# 09-NORStatusLed.net
KiCad netlist of a schematic drawn in Altium Designer
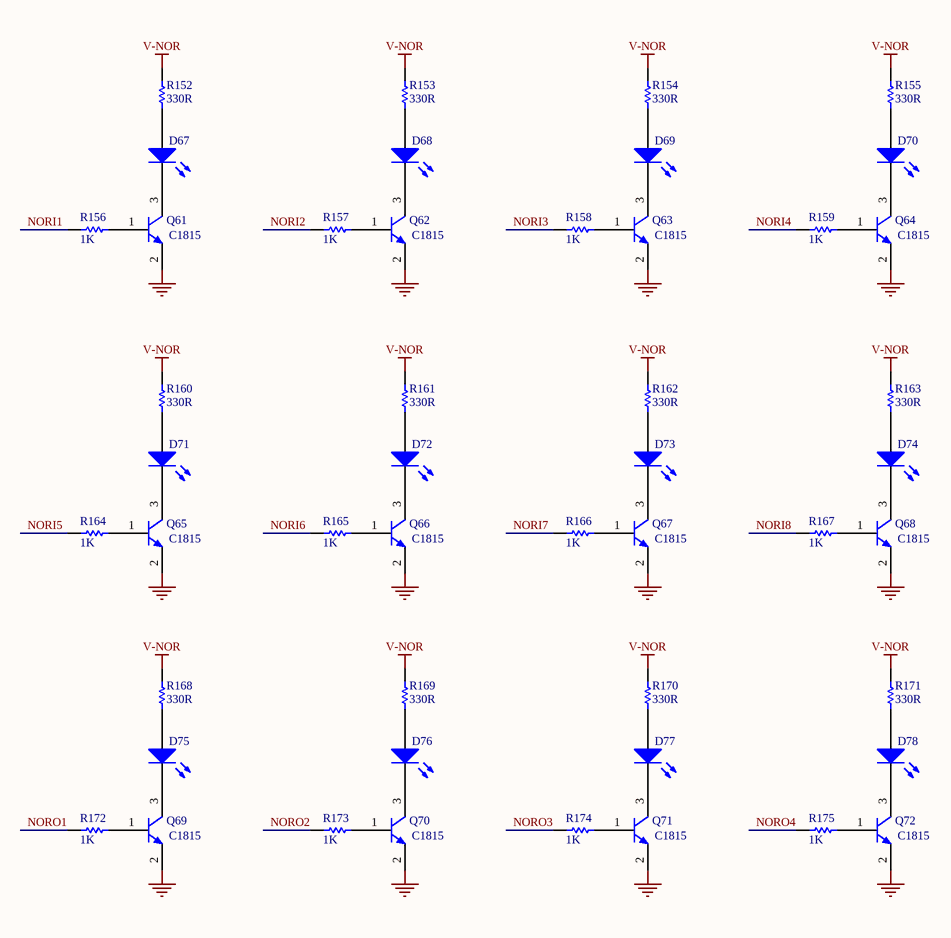
[diagram p0: 09-NORStatusLed.SchDoc]

(export (version "E")
  (design (tool "Eeschema 10.0.6"))
  (components
    (comp (ref "D67")
      (value "LED")
      (footprint "LED-3528")
      (description "Typical RED, GREEN, YELLOW, AMBER GaAs LED")
      (fields (field (name "PUBLISHER") "Altium Limited"))
      (libsource (lib "Miscellaneous Devices") (part "LED2"))
    )
    (comp (ref "D68")
      (value "LED")
      (footprint "LED-3528")
      (description "Typical RED, GREEN, YELLOW, AMBER GaAs LED")
      (fields (field (name "PUBLISHER") "Altium Limited"))
      (libsource (lib "Miscellaneous Devices") (part "LED2"))
    )
    (comp (ref "D69")
      (value "LED")
      (footprint "LED-3528")
      (description "Typical RED, GREEN, YELLOW, AMBER GaAs LED")
      (fields (field (name "PUBLISHER") "Altium Limited"))
      (libsource (lib "Miscellaneous Devices") (part "LED2"))
    )
    (comp (ref "D70")
      (value "LED")
      (footprint "LED-3528")
      (description "Typical RED, GREEN, YELLOW, AMBER GaAs LED")
      (fields (field (name "PUBLISHER") "Altium Limited"))
      (libsource (lib "Miscellaneous Devices") (part "LED2"))
    )
    (comp (ref "D71")
      (value "LED")
      (footprint "LED-3528")
      (description "Typical RED, GREEN, YELLOW, AMBER GaAs LED")
      (fields (field (name "PUBLISHER") "Altium Limited"))
      (libsource (lib "Miscellaneous Devices") (part "LED2"))
    )
    (comp (ref "D72")
      (value "LED")
      (footprint "LED-3528")
      (description "Typical RED, GREEN, YELLOW, AMBER GaAs LED")
      (fields (field (name "PUBLISHER") "Altium Limited"))
      (libsource (lib "Miscellaneous Devices") (part "LED2"))
    )
    (comp (ref "D73")
      (value "LED")
      (footprint "LED-3528")
      (description "Typical RED, GREEN, YELLOW, AMBER GaAs LED")
      (fields (field (name "PUBLISHER") "Altium Limited"))
      (libsource (lib "Miscellaneous Devices") (part "LED2"))
    )
    (comp (ref "D74")
      (value "LED")
      (footprint "LED-3528")
      (description "Typical RED, GREEN, YELLOW, AMBER GaAs LED")
      (fields (field (name "PUBLISHER") "Altium Limited"))
      (libsource (lib "Miscellaneous Devices") (part "LED2"))
    )
    (comp (ref "D75")
      (value "LED")
      (footprint "LED-3528")
      (description "Typical RED, GREEN, YELLOW, AMBER GaAs LED")
      (fields (field (name "PUBLISHER") "Altium Limited"))
      (libsource (lib "Miscellaneous Devices") (part "LED2"))
    )
    (comp (ref "D76")
      (value "LED")
      (footprint "LED-3528")
      (description "Typical RED, GREEN, YELLOW, AMBER GaAs LED")
      (fields (field (name "PUBLISHER") "Altium Limited"))
      (libsource (lib "Miscellaneous Devices") (part "LED2"))
    )
    (comp (ref "D77")
      (value "LED")
      (footprint "LED-3528")
      (description "Typical RED, GREEN, YELLOW, AMBER GaAs LED")
      (fields (field (name "PUBLISHER") "Altium Limited"))
      (libsource (lib "Miscellaneous Devices") (part "LED2"))
    )
    (comp (ref "D78")
      (value "LED")
      (footprint "LED-3528")
      (description "Typical RED, GREEN, YELLOW, AMBER GaAs LED")
      (fields (field (name "PUBLISHER") "Altium Limited"))
      (libsource (lib "Miscellaneous Devices") (part "LED2"))
    )
    (comp (ref "Q61")
      (value "C1815")
      (footprint "SOT23-321")
      (description "NPN Bipolar Transistor")
      (fields (field (name "Comment") "C1815-SMD"))
      (libsource (lib "Miscellaneous Devices") (part "NPN"))
    )
    (comp (ref "Q62")
      (value "C1815")
      (footprint "SOT23-321")
      (description "NPN Bipolar Transistor")
      (fields (field (name "Comment") "C1815-SMD"))
      (libsource (lib "Miscellaneous Devices") (part "NPN"))
    )
    (comp (ref "Q63")
      (value "C1815")
      (footprint "SOT23-321")
      (description "NPN Bipolar Transistor")
      (fields (field (name "Comment") "C1815-SMD"))
      (libsource (lib "Miscellaneous Devices") (part "NPN"))
    )
    (comp (ref "Q64")
      (value "C1815")
      (footprint "SOT23-321")
      (description "NPN Bipolar Transistor")
      (fields (field (name "Comment") "C1815-SMD"))
      (libsource (lib "Miscellaneous Devices") (part "NPN"))
    )
    (comp (ref "Q65")
      (value "C1815")
      (footprint "SOT23-321")
      (description "NPN Bipolar Transistor")
      (fields (field (name "Comment") "C1815-SMD"))
      (libsource (lib "Miscellaneous Devices") (part "NPN"))
    )
    (comp (ref "Q66")
      (value "C1815")
      (footprint "SOT23-321")
      (description "NPN Bipolar Transistor")
      (fields (field (name "Comment") "C1815-SMD"))
      (libsource (lib "Miscellaneous Devices") (part "NPN"))
    )
    (comp (ref "Q67")
      (value "C1815")
      (footprint "SOT23-321")
      (description "NPN Bipolar Transistor")
      (fields (field (name "Comment") "C1815-SMD"))
      (libsource (lib "Miscellaneous Devices") (part "NPN"))
    )
    (comp (ref "Q68")
      (value "C1815")
      (footprint "SOT23-321")
      (description "NPN Bipolar Transistor")
      (fields (field (name "Comment") "C1815-SMD"))
      (libsource (lib "Miscellaneous Devices") (part "NPN"))
    )
    (comp (ref "Q69")
      (value "C1815")
      (footprint "SOT23-321")
      (description "NPN Bipolar Transistor")
      (fields (field (name "Comment") "C1815-SMD"))
      (libsource (lib "Miscellaneous Devices") (part "NPN"))
    )
    (comp (ref "Q70")
      (value "C1815")
      (footprint "SOT23-321")
      (description "NPN Bipolar Transistor")
      (fields (field (name "Comment") "C1815-SMD"))
      (libsource (lib "Miscellaneous Devices") (part "NPN"))
    )
    (comp (ref "Q71")
      (value "C1815")
      (footprint "SOT23-321")
      (description "NPN Bipolar Transistor")
      (fields (field (name "Comment") "C1815-SMD"))
      (libsource (lib "Miscellaneous Devices") (part "NPN"))
    )
    (comp (ref "Q72")
      (value "C1815")
      (footprint "SOT23-321")
      (description "NPN Bipolar Transistor")
      (fields (field (name "Comment") "C1815-SMD"))
      (libsource (lib "Miscellaneous Devices") (part "NPN"))
    )
    (comp (ref "R152")
      (value "330R")
      (footprint "R-0805")
      (description "Resistor")
      (fields (field (name "PUBLISHER") "Altium Limited"))
      (libsource (lib "Miscellaneous Devices") (part "Res1"))
    )
    (comp (ref "R153")
      (value "330R")
      (footprint "R-0805")
      (description "Resistor")
      (fields (field (name "PUBLISHER") "Altium Limited"))
      (libsource (lib "Miscellaneous Devices") (part "Res1"))
    )
    (comp (ref "R154")
      (value "330R")
      (footprint "R-0805")
      (description "Resistor")
      (fields (field (name "PUBLISHER") "Altium Limited"))
      (libsource (lib "Miscellaneous Devices") (part "Res1"))
    )
    (comp (ref "R155")
      (value "330R")
      (footprint "R-0805")
      (description "Resistor")
      (fields (field (name "PUBLISHER") "Altium Limited"))
      (libsource (lib "Miscellaneous Devices") (part "Res1"))
    )
    (comp (ref "R156")
      (value "1K")
      (footprint "R-0805")
      (description "Resistor")
      (fields (field (name "PUBLISHER") "Altium Limited"))
      (libsource (lib "Miscellaneous Devices") (part "Res1"))
    )
    (comp (ref "R157")
      (value "1K")
      (footprint "R-0805")
      (description "Resistor")
      (fields (field (name "PUBLISHER") "Altium Limited"))
      (libsource (lib "Miscellaneous Devices") (part "Res1"))
    )
    (comp (ref "R158")
      (value "1K")
      (footprint "R-0805")
      (description "Resistor")
      (fields (field (name "PUBLISHER") "Altium Limited"))
      (libsource (lib "Miscellaneous Devices") (part "Res1"))
    )
    (comp (ref "R159")
      (value "1K")
      (footprint "R-0805")
      (description "Resistor")
      (fields (field (name "PUBLISHER") "Altium Limited"))
      (libsource (lib "Miscellaneous Devices") (part "Res1"))
    )
    (comp (ref "R160")
      (value "330R")
      (footprint "R-0805")
      (description "Resistor")
      (fields (field (name "PUBLISHER") "Altium Limited"))
      (libsource (lib "Miscellaneous Devices") (part "Res1"))
    )
    (comp (ref "R161")
      (value "330R")
      (footprint "R-0805")
      (description "Resistor")
      (fields (field (name "PUBLISHER") "Altium Limited"))
      (libsource (lib "Miscellaneous Devices") (part "Res1"))
    )
    (comp (ref "R162")
      (value "330R")
      (footprint "R-0805")
      (description "Resistor")
      (fields (field (name "PUBLISHER") "Altium Limited"))
      (libsource (lib "Miscellaneous Devices") (part "Res1"))
    )
    (comp (ref "R163")
      (value "330R")
      (footprint "R-0805")
      (description "Resistor")
      (fields (field (name "PUBLISHER") "Altium Limited"))
      (libsource (lib "Miscellaneous Devices") (part "Res1"))
    )
    (comp (ref "R164")
      (value "1K")
      (footprint "R-0805")
      (description "Resistor")
      (fields (field (name "PUBLISHER") "Altium Limited"))
      (libsource (lib "Miscellaneous Devices") (part "Res1"))
    )
    (comp (ref "R165")
      (value "1K")
      (footprint "R-0805")
      (description "Resistor")
      (fields (field (name "PUBLISHER") "Altium Limited"))
      (libsource (lib "Miscellaneous Devices") (part "Res1"))
    )
    (comp (ref "R166")
      (value "1K")
      (footprint "R-0805")
      (description "Resistor")
      (fields (field (name "PUBLISHER") "Altium Limited"))
      (libsource (lib "Miscellaneous Devices") (part "Res1"))
    )
    (comp (ref "R167")
      (value "1K")
      (footprint "R-0805")
      (description "Resistor")
      (fields (field (name "PUBLISHER") "Altium Limited"))
      (libsource (lib "Miscellaneous Devices") (part "Res1"))
    )
    (comp (ref "R168")
      (value "330R")
      (footprint "R-0805")
      (description "Resistor")
      (fields (field (name "PUBLISHER") "Altium Limited"))
      (libsource (lib "Miscellaneous Devices") (part "Res1"))
    )
    (comp (ref "R169")
      (value "330R")
      (footprint "R-0805")
      (description "Resistor")
      (fields (field (name "PUBLISHER") "Altium Limited"))
      (libsource (lib "Miscellaneous Devices") (part "Res1"))
    )
    (comp (ref "R170")
      (value "330R")
      (footprint "R-0805")
      (description "Resistor")
      (fields (field (name "PUBLISHER") "Altium Limited"))
      (libsource (lib "Miscellaneous Devices") (part "Res1"))
    )
    (comp (ref "R171")
      (value "330R")
      (footprint "R-0805")
      (description "Resistor")
      (fields (field (name "PUBLISHER") "Altium Limited"))
      (libsource (lib "Miscellaneous Devices") (part "Res1"))
    )
    (comp (ref "R172")
      (value "1K")
      (footprint "R-0805")
      (description "Resistor")
      (fields (field (name "PUBLISHER") "Altium Limited"))
      (libsource (lib "Miscellaneous Devices") (part "Res1"))
    )
    (comp (ref "R173")
      (value "1K")
      (footprint "R-0805")
      (description "Resistor")
      (fields (field (name "PUBLISHER") "Altium Limited"))
      (libsource (lib "Miscellaneous Devices") (part "Res1"))
    )
    (comp (ref "R174")
      (value "1K")
      (footprint "R-0805")
      (description "Resistor")
      (fields (field (name "PUBLISHER") "Altium Limited"))
      (libsource (lib "Miscellaneous Devices") (part "Res1"))
    )
    (comp (ref "R175")
      (value "1K")
      (footprint "R-0805")
      (description "Resistor")
      (fields (field (name "PUBLISHER") "Altium Limited"))
      (libsource (lib "Miscellaneous Devices") (part "Res1"))
    )
  )
  (nets
    (net (code "1") (name "/NORI1") (class "Default")
      (node (ref "R156") (pin "2") (pinfunction "2_2") (pintype "passive"))
    )
    (net (code "2") (name "/NORI2") (class "Default")
      (node (ref "R157") (pin "2") (pinfunction "2_2") (pintype "passive"))
    )
    (net (code "3") (name "/NORI3") (class "Default")
      (node (ref "R158") (pin "2") (pinfunction "2_2") (pintype "passive"))
    )
    (net (code "4") (name "/NORI4") (class "Default")
      (node (ref "R159") (pin "2") (pinfunction "2_2") (pintype "passive"))
    )
    (net (code "5") (name "/NORI5") (class "Default")
      (node (ref "R164") (pin "2") (pinfunction "2_2") (pintype "passive"))
    )
    (net (code "6") (name "/NORI6") (class "Default")
      (node (ref "R165") (pin "2") (pinfunction "2_2") (pintype "passive"))
    )
    (net (code "7") (name "/NORI7") (class "Default")
      (node (ref "R166") (pin "2") (pinfunction "2_2") (pintype "passive"))
    )
    (net (code "8") (name "/NORI8") (class "Default")
      (node (ref "R167") (pin "2") (pinfunction "2_2") (pintype "passive"))
    )
    (net (code "9") (name "/NORO1") (class "Default")
      (node (ref "R172") (pin "2") (pinfunction "2_2") (pintype "passive"))
    )
    (net (code "10") (name "/NORO2") (class "Default")
      (node (ref "R173") (pin "2") (pinfunction "2_2") (pintype "passive"))
    )
    (net (code "11") (name "/NORO3") (class "Default")
      (node (ref "R174") (pin "2") (pinfunction "2_2") (pintype "passive"))
    )
    (net (code "12") (name "/NORO4") (class "Default")
      (node (ref "R175") (pin "2") (pinfunction "2_2") (pintype "passive"))
    )
    (net (code "13") (name "GND") (class "Default")
      (node (ref "Q61") (pin "2") (pinfunction "E_2") (pintype "passive"))
      (node (ref "Q62") (pin "2") (pinfunction "E_2") (pintype "passive"))
      (node (ref "Q63") (pin "2") (pinfunction "E_2") (pintype "passive"))
      (node (ref "Q64") (pin "2") (pinfunction "E_2") (pintype "passive"))
      (node (ref "Q65") (pin "2") (pinfunction "E_2") (pintype "passive"))
      (node (ref "Q66") (pin "2") (pinfunction "E_2") (pintype "passive"))
      (node (ref "Q67") (pin "2") (pinfunction "E_2") (pintype "passive"))
      (node (ref "Q68") (pin "2") (pinfunction "E_2") (pintype "passive"))
      (node (ref "Q69") (pin "2") (pinfunction "E_2") (pintype "passive"))
      (node (ref "Q70") (pin "2") (pinfunction "E_2") (pintype "passive"))
      (node (ref "Q71") (pin "2") (pinfunction "E_2") (pintype "passive"))
      (node (ref "Q72") (pin "2") (pinfunction "E_2") (pintype "passive"))
    )
    (net (code "14") (name "Net-(D67-A)") (class "Default")
      (node (ref "D67") (pin "1") (pinfunction "A_1") (pintype "passive"))
      (node (ref "R152") (pin "1") (pinfunction "1_1") (pintype "passive"))
    )
    (net (code "15") (name "Net-(D67-K)") (class "Default")
      (node (ref "D67") (pin "2") (pinfunction "K_2") (pintype "passive"))
      (node (ref "Q61") (pin "3") (pinfunction "C_3") (pintype "passive"))
    )
    (net (code "16") (name "Net-(D68-A)") (class "Default")
      (node (ref "D68") (pin "1") (pinfunction "A_1") (pintype "passive"))
      (node (ref "R153") (pin "1") (pinfunction "1_1") (pintype "passive"))
    )
    (net (code "17") (name "Net-(D68-K)") (class "Default")
      (node (ref "D68") (pin "2") (pinfunction "K_2") (pintype "passive"))
      (node (ref "Q62") (pin "3") (pinfunction "C_3") (pintype "passive"))
    )
    (net (code "18") (name "Net-(D69-A)") (class "Default")
      (node (ref "D69") (pin "1") (pinfunction "A_1") (pintype "passive"))
      (node (ref "R154") (pin "1") (pinfunction "1_1") (pintype "passive"))
    )
    (net (code "19") (name "Net-(D69-K)") (class "Default")
      (node (ref "D69") (pin "2") (pinfunction "K_2") (pintype "passive"))
      (node (ref "Q63") (pin "3") (pinfunction "C_3") (pintype "passive"))
    )
    (net (code "20") (name "Net-(D70-A)") (class "Default")
      (node (ref "D70") (pin "1") (pinfunction "A_1") (pintype "passive"))
      (node (ref "R155") (pin "1") (pinfunction "1_1") (pintype "passive"))
    )
    (net (code "21") (name "Net-(D70-K)") (class "Default")
      (node (ref "D70") (pin "2") (pinfunction "K_2") (pintype "passive"))
      (node (ref "Q64") (pin "3") (pinfunction "C_3") (pintype "passive"))
    )
    (net (code "22") (name "Net-(D71-A)") (class "Default")
      (node (ref "D71") (pin "1") (pinfunction "A_1") (pintype "passive"))
      (node (ref "R160") (pin "1") (pinfunction "1_1") (pintype "passive"))
    )
    (net (code "23") (name "Net-(D71-K)") (class "Default")
      (node (ref "D71") (pin "2") (pinfunction "K_2") (pintype "passive"))
      (node (ref "Q65") (pin "3") (pinfunction "C_3") (pintype "passive"))
    )
    (net (code "24") (name "Net-(D72-A)") (class "Default")
      (node (ref "D72") (pin "1") (pinfunction "A_1") (pintype "passive"))
      (node (ref "R161") (pin "1") (pinfunction "1_1") (pintype "passive"))
    )
    (net (code "25") (name "Net-(D72-K)") (class "Default")
      (node (ref "D72") (pin "2") (pinfunction "K_2") (pintype "passive"))
      (node (ref "Q66") (pin "3") (pinfunction "C_3") (pintype "passive"))
    )
    (net (code "26") (name "Net-(D73-A)") (class "Default")
      (node (ref "D73") (pin "1") (pinfunction "A_1") (pintype "passive"))
      (node (ref "R162") (pin "1") (pinfunction "1_1") (pintype "passive"))
    )
    (net (code "27") (name "Net-(D73-K)") (class "Default")
      (node (ref "D73") (pin "2") (pinfunction "K_2") (pintype "passive"))
      (node (ref "Q67") (pin "3") (pinfunction "C_3") (pintype "passive"))
    )
    (net (code "28") (name "Net-(D74-A)") (class "Default")
      (node (ref "D74") (pin "1") (pinfunction "A_1") (pintype "passive"))
      (node (ref "R163") (pin "1") (pinfunction "1_1") (pintype "passive"))
    )
    (net (code "29") (name "Net-(D74-K)") (class "Default")
      (node (ref "D74") (pin "2") (pinfunction "K_2") (pintype "passive"))
      (node (ref "Q68") (pin "3") (pinfunction "C_3") (pintype "passive"))
    )
    (net (code "30") (name "Net-(D75-A)") (class "Default")
      (node (ref "D75") (pin "1") (pinfunction "A_1") (pintype "passive"))
      (node (ref "R168") (pin "1") (pinfunction "1_1") (pintype "passive"))
    )
    (net (code "31") (name "Net-(D75-K)") (class "Default")
      (node (ref "D75") (pin "2") (pinfunction "K_2") (pintype "passive"))
      (node (ref "Q69") (pin "3") (pinfunction "C_3") (pintype "passive"))
    )
    (net (code "32") (name "Net-(D76-A)") (class "Default")
      (node (ref "D76") (pin "1") (pinfunction "A_1") (pintype "passive"))
      (node (ref "R169") (pin "1") (pinfunction "1_1") (pintype "passive"))
    )
    (net (code "33") (name "Net-(D76-K)") (class "Default")
      (node (ref "D76") (pin "2") (pinfunction "K_2") (pintype "passive"))
      (node (ref "Q70") (pin "3") (pinfunction "C_3") (pintype "passive"))
    )
    (net (code "34") (name "Net-(D77-A)") (class "Default")
      (node (ref "D77") (pin "1") (pinfunction "A_1") (pintype "passive"))
      (node (ref "R170") (pin "1") (pinfunction "1_1") (pintype "passive"))
    )
    (net (code "35") (name "Net-(D77-K)") (class "Default")
      (node (ref "D77") (pin "2") (pinfunction "K_2") (pintype "passive"))
      (node (ref "Q71") (pin "3") (pinfunction "C_3") (pintype "passive"))
    )
    (net (code "36") (name "Net-(D78-A)") (class "Default")
      (node (ref "D78") (pin "1") (pinfunction "A_1") (pintype "passive"))
      (node (ref "R171") (pin "1") (pinfunction "1_1") (pintype "passive"))
    )
    (net (code "37") (name "Net-(D78-K)") (class "Default")
      (node (ref "D78") (pin "2") (pinfunction "K_2") (pintype "passive"))
      (node (ref "Q72") (pin "3") (pinfunction "C_3") (pintype "passive"))
    )
    (net (code "38") (name "Net-(Q61-B)") (class "Default")
      (node (ref "Q61") (pin "1") (pinfunction "B_1") (pintype "passive"))
      (node (ref "R156") (pin "1") (pinfunction "1_1") (pintype "passive"))
    )
    (net (code "39") (name "Net-(Q62-B)") (class "Default")
      (node (ref "Q62") (pin "1") (pinfunction "B_1") (pintype "passive"))
      (node (ref "R157") (pin "1") (pinfunction "1_1") (pintype "passive"))
    )
    (net (code "40") (name "Net-(Q63-B)") (class "Default")
      (node (ref "Q63") (pin "1") (pinfunction "B_1") (pintype "passive"))
      (node (ref "R158") (pin "1") (pinfunction "1_1") (pintype "passive"))
    )
    (net (code "41") (name "Net-(Q64-B)") (class "Default")
      (node (ref "Q64") (pin "1") (pinfunction "B_1") (pintype "passive"))
      (node (ref "R159") (pin "1") (pinfunction "1_1") (pintype "passive"))
    )
    (net (code "42") (name "Net-(Q65-B)") (class "Default")
      (node (ref "Q65") (pin "1") (pinfunction "B_1") (pintype "passive"))
      (node (ref "R164") (pin "1") (pinfunction "1_1") (pintype "passive"))
    )
    (net (code "43") (name "Net-(Q66-B)") (class "Default")
      (node (ref "Q66") (pin "1") (pinfunction "B_1") (pintype "passive"))
      (node (ref "R165") (pin "1") (pinfunction "1_1") (pintype "passive"))
    )
    (net (code "44") (name "Net-(Q67-B)") (class "Default")
      (node (ref "Q67") (pin "1") (pinfunction "B_1") (pintype "passive"))
      (node (ref "R166") (pin "1") (pinfunction "1_1") (pintype "passive"))
    )
    (net (code "45") (name "Net-(Q68-B)") (class "Default")
      (node (ref "Q68") (pin "1") (pinfunction "B_1") (pintype "passive"))
      (node (ref "R167") (pin "1") (pinfunction "1_1") (pintype "passive"))
    )
    (net (code "46") (name "Net-(Q69-B)") (class "Default")
      (node (ref "Q69") (pin "1") (pinfunction "B_1") (pintype "passive"))
      (node (ref "R172") (pin "1") (pinfunction "1_1") (pintype "passive"))
    )
    (net (code "47") (name "Net-(Q70-B)") (class "Default")
      (node (ref "Q70") (pin "1") (pinfunction "B_1") (pintype "passive"))
      (node (ref "R173") (pin "1") (pinfunction "1_1") (pintype "passive"))
    )
    (net (code "48") (name "Net-(Q71-B)") (class "Default")
      (node (ref "Q71") (pin "1") (pinfunction "B_1") (pintype "passive"))
      (node (ref "R174") (pin "1") (pinfunction "1_1") (pintype "passive"))
    )
    (net (code "49") (name "Net-(Q72-B)") (class "Default")
      (node (ref "Q72") (pin "1") (pinfunction "B_1") (pintype "passive"))
      (node (ref "R175") (pin "1") (pinfunction "1_1") (pintype "passive"))
    )
    (net (code "50") (name "V-NOR") (class "Default")
      (node (ref "R152") (pin "2") (pinfunction "2_2") (pintype "passive"))
      (node (ref "R153") (pin "2") (pinfunction "2_2") (pintype "passive"))
      (node (ref "R154") (pin "2") (pinfunction "2_2") (pintype "passive"))
      (node (ref "R155") (pin "2") (pinfunction "2_2") (pintype "passive"))
      (node (ref "R160") (pin "2") (pinfunction "2_2") (pintype "passive"))
      (node (ref "R161") (pin "2") (pinfunction "2_2") (pintype "passive"))
      (node (ref "R162") (pin "2") (pinfunction "2_2") (pintype "passive"))
      (node (ref "R163") (pin "2") (pinfunction "2_2") (pintype "passive"))
      (node (ref "R168") (pin "2") (pinfunction "2_2") (pintype "passive"))
      (node (ref "R169") (pin "2") (pinfunction "2_2") (pintype "passive"))
      (node (ref "R170") (pin "2") (pinfunction "2_2") (pintype "passive"))
      (node (ref "R171") (pin "2") (pinfunction "2_2") (pintype "passive"))
    )
  )
)
